# ESP_SoC.net
KiCad netlist of a schematic drawn in Altium Designer
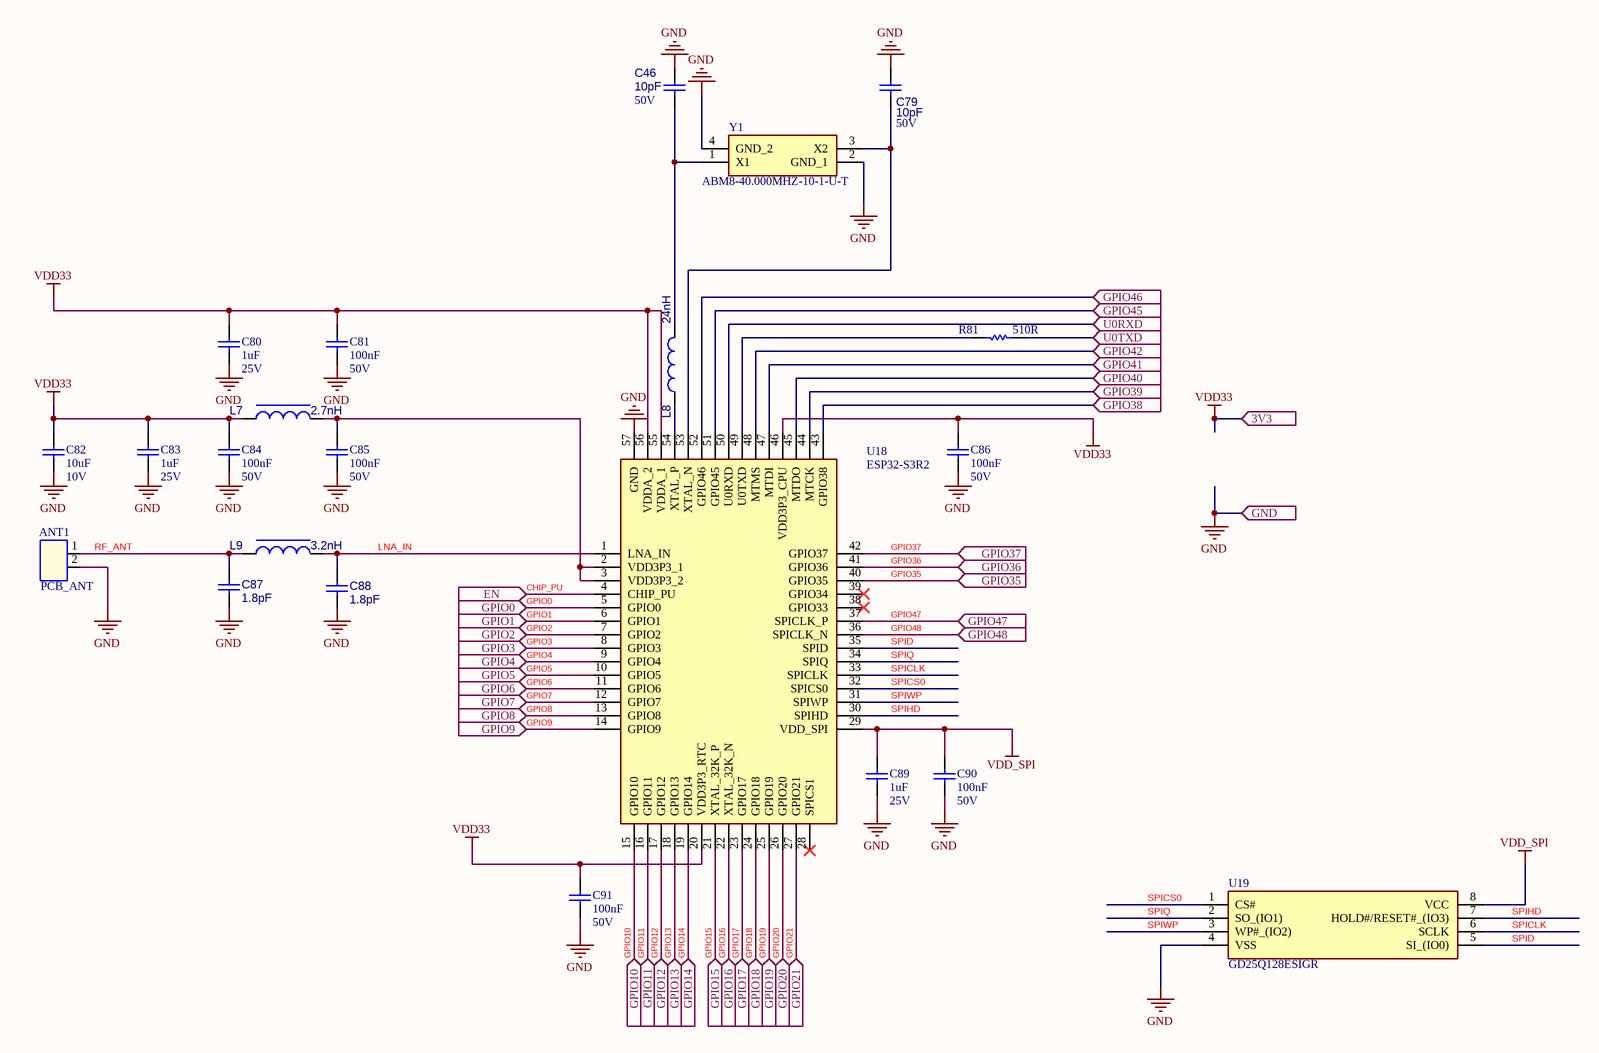
[diagram p0: ESP_SoC.SchDoc]

(export (version "E")
  (design (tool "Eeschema 10.0.6"))
  (components
    (comp (ref "ANT1") (value "PCB_ANT") (footprint "MINI-ANT-TYPEB") (libsource (lib "*") (part "PCB_ANT")))
    (comp (ref "C46")
      (value "10pF")
      (footprint "CAP_0603")
      (description "MLCC (1608) 0603 10pF 50VDC ±5% C0G (NP0)")
      (fields
        (field (name "MANUFACTURER") "SAMSUNG")
        (field (name "MANUFACTURER PART NUMBER") "CL10C100JB8NNNC")
        (field (name "VOLTAGE") "50V")
      )
      (libsource (lib "Passives") (part "CL10C100JB8NNNC"))
    )
    (comp (ref "C79")
      (value "10pF")
      (footprint "CAP_0603")
      (description "MLCC (1608) 0603 10pF 50VDC ±5% C0G (NP0)")
      (fields
        (field (name "MANUFACTURER") "SAMSUNG")
        (field (name "MANUFACTURER PART NUMBER") "CL10C100JB8NNNC")
        (field (name "VOLTAGE") "50V")
      )
      (libsource (lib "Passives") (part "CL10C100JB8NNNC"))
    )
    (comp (ref "C80")
      (value "1uF")
      (footprint "CAP_0603")
      (description "CAP CER 1UF 25VDC %10 X5R SMD")
      (fields
        (field (name "VOLTAGE") "25V")
        (field (name "MANUFACTURER") "Samsung")
        (field (name "MANUFACTURER PART NUMBER") "CL10A105KA8NNNC")
      )
      (libsource (lib "open-components") (part "CAP"))
    )
    (comp (ref "C81")
      (value "100nF")
      (footprint "CAP_0603")
      (description "CAP CER 100nF 50VDC %10 X7R SMD")
      (fields
        (field (name "VOLTAGE") "50V")
        (field (name "MANUFACTURER") "Samsung")
        (field (name "MANUFACTURER PART NUMBER") "CL10B104KB8NNNL")
      )
      (libsource (lib "open-components") (part "CAP"))
    )
    (comp (ref "C82")
      (value "10uF")
      (footprint "CAP_0603")
      (description "MLCC (1608) 0603 10uF 10VDC ±20% X5R")
      (fields
        (field (name "VOLTAGE") "10V")
        (field (name "MANUFACTURER") "Samsung")
        (field (name "MANUFACTURER PART NUMBER") "CL10A106MP8NNNC")
      )
      (libsource (lib "open-components") (part "CAP"))
    )
    (comp (ref "C83")
      (value "1uF")
      (footprint "CAP_0603")
      (description "CAP CER 1UF 25VDC %10 X5R SMD")
      (fields
        (field (name "VOLTAGE") "25V")
        (field (name "MANUFACTURER") "Samsung")
        (field (name "MANUFACTURER PART NUMBER") "CL10A105KA8NNNC")
      )
      (libsource (lib "open-components") (part "CAP"))
    )
    (comp (ref "C84")
      (value "100nF")
      (footprint "CAP_0603")
      (description "CAP CER 100nF 50VDC %10 X7R SMD")
      (fields
        (field (name "VOLTAGE") "50V")
        (field (name "MANUFACTURER") "Samsung")
        (field (name "MANUFACTURER PART NUMBER") "CL10B104KB8NNNL")
      )
      (libsource (lib "open-components") (part "CAP"))
    )
    (comp (ref "C85")
      (value "100nF")
      (footprint "CAP_0603")
      (description "CAP CER 100nF 50VDC %10 X7R SMD")
      (fields
        (field (name "VOLTAGE") "50V")
        (field (name "MANUFACTURER") "Samsung")
        (field (name "MANUFACTURER PART NUMBER") "CL10B104KB8NNNL")
      )
      (libsource (lib "open-components") (part "CAP"))
    )
    (comp (ref "C86")
      (value "100nF")
      (footprint "CAP_0603")
      (description "CAP CER 100nF 50VDC %10 X7R SMD")
      (fields
        (field (name "VOLTAGE") "50V")
        (field (name "MANUFACTURER") "Samsung")
        (field (name "MANUFACTURER PART NUMBER") "CL10B104KB8NNNL")
      )
      (libsource (lib "open-components") (part "CAP"))
    )
    (comp (ref "C87")
      (value "1.8pF")
      (footprint "CAP_0402")
      (description "MLCC 1.8 pF 50 VDC 0.25 pF 0402 C0G (NP0)")
      (fields
        (field (name "VOLTAGE") "0402 (1005 Metric)")
        (field (name "MANUFACTURER") "Murata Electronics")
      )
      (libsource (lib "Passives") (part "CL05B104KB5NNNC"))
    )
    (comp (ref "C88")
      (value "1.8pF")
      (footprint "CAP_0402")
      (description "MLCC 1.8 pF 50 VDC 0.25 pF 0402 C0G (NP0)")
      (fields
        (field (name "VOLTAGE") "0402 (1005 Metric)")
        (field (name "MANUFACTURER") "Murata Electronics")
      )
      (libsource (lib "Passives") (part "CL05B104KB5NNNC"))
    )
    (comp (ref "C89")
      (value "1uF")
      (footprint "CAP_0603")
      (description "CAP CER 1UF 25VDC %10 X5R SMD")
      (fields
        (field (name "VOLTAGE") "25V")
        (field (name "MANUFACTURER") "Samsung")
        (field (name "MANUFACTURER PART NUMBER") "CL10A105KA8NNNC")
      )
      (libsource (lib "open-components") (part "CAP"))
    )
    (comp (ref "C90")
      (value "100nF")
      (footprint "CAP_0603")
      (description "CAP CER 100nF 50VDC %10 X7R SMD")
      (fields
        (field (name "VOLTAGE") "50V")
        (field (name "MANUFACTURER") "Samsung")
        (field (name "MANUFACTURER PART NUMBER") "CL10B104KB8NNNL")
      )
      (libsource (lib "open-components") (part "CAP"))
    )
    (comp (ref "C91")
      (value "100nF")
      (footprint "CAP_0603")
      (description "CAP CER 100nF 50VDC %10 X7R SMD")
      (fields
        (field (name "VOLTAGE") "50V")
        (field (name "MANUFACTURER") "Samsung")
        (field (name "MANUFACTURER PART NUMBER") "CL10B104KB8NNNL")
      )
      (libsource (lib "open-components") (part "CAP"))
    )
    (comp (ref "L7")
      (value "2.7nH")
      (footprint "res_0603")
      (description "INDUCTOR FIXED 2.7nH 500mA")
      (fields
        (field (name "MANUFACTURER") "PANASONIC(EUROPE)")
        (field (name "MANUFACTURER PART NUMBER") "ELJRE2N7DFA")
      )
      (libsource (lib "Passives") (part "7447709150"))
    )
    (comp (ref "L8")
      (value "24nH")
      (footprint "res_0603")
      (description "INDUCTOR FIXED 0603 24NH")
      (fields
        (field (name "MANUFACTURER") "MURATA")
        (field (name "MANUFACTURER PART NUMBER") "LQW18AN24NJ00J")
      )
      (libsource (lib "Passives") (part "7447709150"))
    )
    (comp (ref "L9")
      (value "3.2nH")
      (footprint "res_0402")
      (description "FIXED IND 3.2NH 500MA 0.17OHM SM")
      (fields
        (field (name "MANUFACTURER") "Murata Electronics")
        (field (name "MANUFACTURER PART NUMBER") "LQW15AN3N2B0ZD")
      )
      (libsource (lib "Passives") (part "7447709150"))
    )
    (comp (ref "R81")
      (value "510R")
      (footprint "R0603")
      (description "RES.(1608) 0603 510 Ohms 5% 1/10W-S 100PPM")
      (fields
        (field (name "MANUFACTURER") "ROYALOHM")
        (field (name "MANUFACTURER PART NUMBER") "0603SAJ0511T5E")
      )
      (libsource (lib "open-components") (part "RES"))
    )
    (comp (ref "U18")
      (value "ESP32-S3R2")
      (footprint "SamacSys:QFN40P700X700X90-57N-D")
      (description "IC RF TXRX+MCU BLE 56QFN")
      (fields (field (name "MANUFACTURER") "Espressif Systems"))
      (libsource (lib "*") (part "ESP32-S3"))
    )
    (comp (ref "U19")
      (value "GD25Q128ESIGR")
      (footprint "SamacSys:SOIC127P790X216-8N")
      (description "IC FLASH 128MBIT SPI/QUAD 8SOP")
      (fields (field (name "MANUFACTURER") "GigaDevice Semiconductor (HK) Limited"))
      (libsource (lib "*") (part "GD25Q128ESIGR"))
    )
    (comp (ref "Y1")
      (value "ABM8-40.000MHZ-10-1-U-T")
      (footprint "SamacSys:ABM810000MHZ12D2W")
      (description "CRYSTAL 40.0000MHZ 10PF SMD")
      (fields (field (name "MANUFACTURER") "ABRACON"))
      (libsource (lib "*") (part "ABM8-40.000MHZ-10-1-U-T"))
    )
  )
  (nets
    (net (code "1") (name "/CHIP_PU") (class "Default")
      (node (ref "U18") (pin "4") (pinfunction "CHIP_PU_4") (pintype "passive"))
    )
    (net (code "2") (name "/GPIO0") (class "Default")
      (node (ref "U18") (pin "5") (pinfunction "GPIO0_5") (pintype "passive"))
    )
    (net (code "3") (name "/GPIO1") (class "Default")
      (node (ref "U18") (pin "6") (pinfunction "GPIO1_6") (pintype "passive"))
    )
    (net (code "4") (name "/GPIO2") (class "Default")
      (node (ref "U18") (pin "7") (pinfunction "GPIO2_7") (pintype "passive"))
    )
    (net (code "5") (name "/GPIO3") (class "Default")
      (node (ref "U18") (pin "8") (pinfunction "GPIO3_8") (pintype "passive"))
    )
    (net (code "6") (name "/GPIO4") (class "Default")
      (node (ref "U18") (pin "9") (pinfunction "GPIO4_9") (pintype "passive"))
    )
    (net (code "7") (name "/GPIO5") (class "Default")
      (node (ref "U18") (pin "10") (pinfunction "GPIO5_10") (pintype "passive"))
    )
    (net (code "8") (name "/GPIO6") (class "Default")
      (node (ref "U18") (pin "11") (pinfunction "GPIO6_11") (pintype "passive"))
    )
    (net (code "9") (name "/GPIO7") (class "Default")
      (node (ref "U18") (pin "12") (pinfunction "GPIO7_12") (pintype "passive"))
    )
    (net (code "10") (name "/GPIO8") (class "Default")
      (node (ref "U18") (pin "13") (pinfunction "GPIO8_13") (pintype "passive"))
    )
    (net (code "11") (name "/GPIO9") (class "Default")
      (node (ref "U18") (pin "14") (pinfunction "GPIO9_14") (pintype "passive"))
    )
    (net (code "12") (name "/GPIO10") (class "Default")
      (node (ref "U18") (pin "15") (pinfunction "GPIO10_15") (pintype "passive"))
    )
    (net (code "13") (name "/GPIO11") (class "Default")
      (node (ref "U18") (pin "16") (pinfunction "GPIO11_16") (pintype "passive"))
    )
    (net (code "14") (name "/GPIO12") (class "Default")
      (node (ref "U18") (pin "17") (pinfunction "GPIO12_17") (pintype "passive"))
    )
    (net (code "15") (name "/GPIO13") (class "Default")
      (node (ref "U18") (pin "18") (pinfunction "GPIO13_18") (pintype "passive"))
    )
    (net (code "16") (name "/GPIO14") (class "Default")
      (node (ref "U18") (pin "19") (pinfunction "GPIO14_19") (pintype "passive"))
    )
    (net (code "17") (name "/GPIO15") (class "Default")
      (node (ref "U18") (pin "21") (pinfunction "XTAL_32K_P_21") (pintype "passive"))
    )
    (net (code "18") (name "/GPIO16") (class "Default")
      (node (ref "U18") (pin "22") (pinfunction "XTAL_32K_N_22") (pintype "passive"))
    )
    (net (code "19") (name "/GPIO17") (class "Default")
      (node (ref "U18") (pin "23") (pinfunction "GPIO17_23") (pintype "passive"))
    )
    (net (code "20") (name "/GPIO18") (class "Default")
      (node (ref "U18") (pin "24") (pinfunction "GPIO18_24") (pintype "passive"))
    )
    (net (code "21") (name "/GPIO19") (class "Default")
      (node (ref "U18") (pin "25") (pinfunction "GPIO19_25") (pintype "passive"))
    )
    (net (code "22") (name "/GPIO20") (class "Default")
      (node (ref "U18") (pin "26") (pinfunction "GPIO20_26") (pintype "passive"))
    )
    (net (code "23") (name "/GPIO21") (class "Default")
      (node (ref "U18") (pin "27") (pinfunction "GPIO21_27") (pintype "passive"))
    )
    (net (code "24") (name "/GPIO35") (class "Default")
      (node (ref "U18") (pin "40") (pinfunction "GPIO35_40") (pintype "passive"))
    )
    (net (code "25") (name "/GPIO36") (class "Default")
      (node (ref "U18") (pin "41") (pinfunction "GPIO36_41") (pintype "passive"))
    )
    (net (code "26") (name "/GPIO37") (class "Default")
      (node (ref "U18") (pin "42") (pinfunction "GPIO37_42") (pintype "passive"))
    )
    (net (code "27") (name "/GPIO38") (class "Default")
      (node (ref "U18") (pin "43") (pinfunction "GPIO38_43") (pintype "passive"))
    )
    (net (code "28") (name "/GPIO39") (class "Default")
      (node (ref "U18") (pin "44") (pinfunction "MTCK_44") (pintype "passive"))
    )
    (net (code "29") (name "/GPIO40") (class "Default")
      (node (ref "U18") (pin "45") (pinfunction "MTDO_45") (pintype "passive"))
    )
    (net (code "30") (name "/GPIO41") (class "Default")
      (node (ref "U18") (pin "47") (pinfunction "MTDI_47") (pintype "passive"))
    )
    (net (code "31") (name "/GPIO42") (class "Default")
      (node (ref "U18") (pin "48") (pinfunction "MTMS_48") (pintype "passive"))
    )
    (net (code "32") (name "/GPIO45") (class "Default")
      (node (ref "U18") (pin "51") (pinfunction "GPIO45_51") (pintype "passive"))
    )
    (net (code "33") (name "/GPIO46") (class "Default")
      (node (ref "U18") (pin "52") (pinfunction "GPIO46_52") (pintype "passive"))
    )
    (net (code "34") (name "/GPIO47") (class "Default")
      (node (ref "U18") (pin "37") (pinfunction "SPICLK_P_37") (pintype "passive"))
    )
    (net (code "35") (name "/GPIO48") (class "Default")
      (node (ref "U18") (pin "36") (pinfunction "SPICLK_N_36") (pintype "passive"))
    )
    (net (code "36") (name "/LNA_IN") (class "Default")
      (node (ref "C88") (pin "1") (pinfunction "1_1") (pintype "passive"))
      (node (ref "L9") (pin "2") (pinfunction "2_2") (pintype "passive"))
      (node (ref "U18") (pin "1") (pinfunction "LNA_IN_1") (pintype "passive"))
    )
    (net (code "37") (name "/RF_ANT") (class "Default")
      (node (ref "ANT1") (pin "1") (pinfunction "1_1") (pintype "passive"))
      (node (ref "C87") (pin "1") (pinfunction "1_1") (pintype "passive"))
      (node (ref "L9") (pin "1") (pinfunction "1_1") (pintype "passive"))
    )
    (net (code "38") (name "/SPICLK") (class "Default")
      (node (ref "U18") (pin "33") (pinfunction "SPICLK_33") (pintype "passive"))
      (node (ref "U19") (pin "6") (pinfunction "SCLK_6") (pintype "passive"))
    )
    (net (code "39") (name "/SPICS0") (class "Default")
      (node (ref "U18") (pin "32") (pinfunction "SPICS0_32") (pintype "passive"))
      (node (ref "U19") (pin "1") (pinfunction "CS#_1") (pintype "passive"))
    )
    (net (code "40") (name "/SPID") (class "Default")
      (node (ref "U18") (pin "35") (pinfunction "SPID_35") (pintype "passive"))
      (node (ref "U19") (pin "5") (pinfunction "SI_(IO0)_5") (pintype "passive"))
    )
    (net (code "41") (name "/SPIHD") (class "Default")
      (node (ref "U18") (pin "30") (pinfunction "SPIHD_30") (pintype "passive"))
      (node (ref "U19") (pin "7") (pinfunction "HOLD#/RESET#_(IO3)_7") (pintype "passive"))
    )
    (net (code "42") (name "/SPIQ") (class "Default")
      (node (ref "U18") (pin "34") (pinfunction "SPIQ_34") (pintype "passive"))
      (node (ref "U19") (pin "2") (pinfunction "SO_(IO1)_2") (pintype "passive"))
    )
    (net (code "43") (name "/SPIWP") (class "Default")
      (node (ref "U18") (pin "31") (pinfunction "SPIWP_31") (pintype "passive"))
      (node (ref "U19") (pin "3") (pinfunction "WP#_(IO2)_3") (pintype "passive"))
    )
    (net (code "44") (name "/U0RXD") (class "Default")
      (node (ref "U18") (pin "50") (pinfunction "U0RXD_50") (pintype "passive"))
    )
    (net (code "45") (name "/U0TXD") (class "Default")
      (node (ref "R81") (pin "1") (pinfunction "1_1") (pintype "passive"))
    )
    (net (code "46") (name "GND") (class "Default")
      (node (ref "ANT1") (pin "2") (pinfunction "2_2") (pintype "passive"))
      (node (ref "C46") (pin "1") (pinfunction "1_1") (pintype "passive"))
      (node (ref "C79") (pin "1") (pinfunction "1_1") (pintype "passive"))
      (node (ref "C80") (pin "2") (pinfunction "2_2") (pintype "passive"))
      (node (ref "C81") (pin "2") (pinfunction "2_2") (pintype "passive"))
      (node (ref "C82") (pin "2") (pinfunction "2_2") (pintype "passive"))
      (node (ref "C83") (pin "2") (pinfunction "2_2") (pintype "passive"))
      (node (ref "C84") (pin "2") (pinfunction "2_2") (pintype "passive"))
      (node (ref "C85") (pin "2") (pinfunction "2_2") (pintype "passive"))
      (node (ref "C86") (pin "2") (pinfunction "2_2") (pintype "passive"))
      (node (ref "C87") (pin "2") (pinfunction "2_2") (pintype "passive"))
      (node (ref "C88") (pin "2") (pinfunction "2_2") (pintype "passive"))
      (node (ref "C89") (pin "2") (pinfunction "2_2") (pintype "passive"))
      (node (ref "C90") (pin "2") (pinfunction "2_2") (pintype "passive"))
      (node (ref "C91") (pin "2") (pinfunction "2_2") (pintype "passive"))
      (node (ref "U18") (pin "57") (pinfunction "GND_57") (pintype "passive"))
      (node (ref "U19") (pin "4") (pinfunction "VSS_4") (pintype "passive"))
      (node (ref "Y1") (pin "2") (pinfunction "GND_1_2") (pintype "passive"))
      (node (ref "Y1") (pin "4") (pinfunction "GND_2_4") (pintype "passive"))
    )
    (net (code "47") (name "Net-(U18-U0TXD)") (class "Default")
      (node (ref "R81") (pin "2") (pinfunction "2_2") (pintype "passive"))
      (node (ref "U18") (pin "49") (pinfunction "U0TXD_49") (pintype "passive"))
    )
    (net (code "48") (name "Net-(U18-VDD3P3_1)") (class "Default")
      (node (ref "C85") (pin "1") (pinfunction "1_1") (pintype "passive"))
      (node (ref "L7") (pin "2") (pinfunction "2_2") (pintype "passive"))
      (node (ref "U18") (pin "2") (pinfunction "VDD3P3_1_2") (pintype "passive"))
      (node (ref "U18") (pin "3") (pinfunction "VDD3P3_2_3") (pintype "passive"))
    )
    (net (code "49") (name "Net-(U18-XTAL_N)") (class "Default")
      (node (ref "C79") (pin "2") (pinfunction "2_2") (pintype "passive"))
      (node (ref "U18") (pin "53") (pinfunction "XTAL_N_53") (pintype "passive"))
      (node (ref "Y1") (pin "3") (pinfunction "X2_3") (pintype "passive"))
    )
    (net (code "50") (name "Net-(U18-XTAL_P)") (class "Default")
      (node (ref "L8") (pin "1") (pinfunction "1_1") (pintype "passive"))
      (node (ref "U18") (pin "54") (pinfunction "XTAL_P_54") (pintype "passive"))
    )
    (net (code "51") (name "Net-(Y1-X1)") (class "Default")
      (node (ref "C46") (pin "2") (pinfunction "2_2") (pintype "passive"))
      (node (ref "L8") (pin "2") (pinfunction "2_2") (pintype "passive"))
      (node (ref "Y1") (pin "1") (pinfunction "X1_1") (pintype "passive"))
    )
    (net (code "52") (name "VDD33") (class "Default")
      (node (ref "C80") (pin "1") (pinfunction "1_1") (pintype "passive"))
      (node (ref "C81") (pin "1") (pinfunction "1_1") (pintype "passive"))
      (node (ref "C82") (pin "1") (pinfunction "1_1") (pintype "passive"))
      (node (ref "C83") (pin "1") (pinfunction "1_1") (pintype "passive"))
      (node (ref "C84") (pin "1") (pinfunction "1_1") (pintype "passive"))
      (node (ref "C86") (pin "1") (pinfunction "1_1") (pintype "passive"))
      (node (ref "C91") (pin "1") (pinfunction "1_1") (pintype "passive"))
      (node (ref "L7") (pin "1") (pinfunction "1_1") (pintype "passive"))
      (node (ref "U18") (pin "20") (pinfunction "VDD3P3_RTC_20") (pintype "passive"))
      (node (ref "U18") (pin "46") (pinfunction "VDD3P3_CPU_46") (pintype "passive"))
      (node (ref "U18") (pin "55") (pinfunction "VDDA_1_55") (pintype "passive"))
      (node (ref "U18") (pin "56") (pinfunction "VDDA_2_56") (pintype "passive"))
    )
    (net (code "53") (name "VDD_SPI") (class "Default")
      (node (ref "C89") (pin "1") (pinfunction "1_1") (pintype "passive"))
      (node (ref "C90") (pin "1") (pinfunction "1_1") (pintype "passive"))
      (node (ref "U18") (pin "29") (pinfunction "VDD_SPI_29") (pintype "passive"))
      (node (ref "U19") (pin "8") (pinfunction "VCC_8") (pintype "passive"))
    )
    (net (code "54") (name "unconnected-(U18-GPIO33-Pad38)") (class "Default")
      (node (ref "U18") (pin "38") (pinfunction "GPIO33_38") (pintype "passive+no_connect"))
    )
    (net (code "55") (name "unconnected-(U18-GPIO34-Pad39)") (class "Default")
      (node (ref "U18") (pin "39") (pinfunction "GPIO34_39") (pintype "passive+no_connect"))
    )
    (net (code "56") (name "unconnected-(U18-SPICS1-Pad28)") (class "Default")
      (node (ref "U18") (pin "28") (pinfunction "SPICS1_28") (pintype "passive+no_connect"))
    )
  )
)
